# 2576.net
KiCad netlist of a schematic drawn in Altium Designer
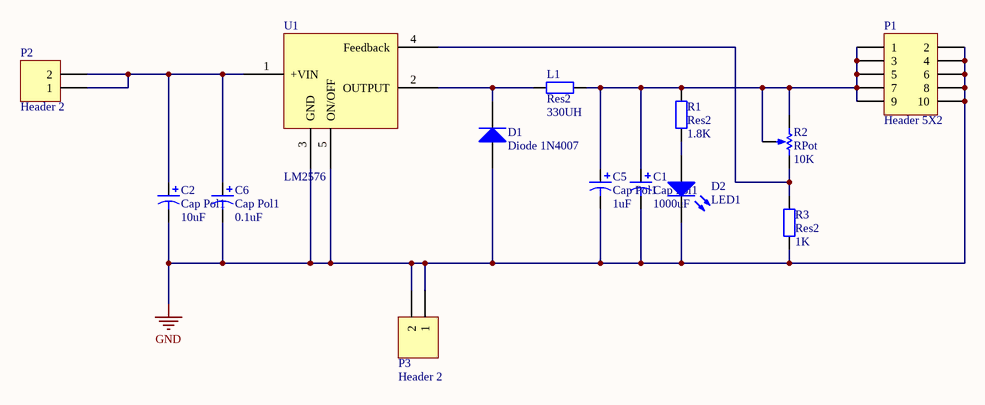
[diagram p0: 2576电压可调电路.SchDoc]

(export (version "E")
  (design (tool "Eeschema 10.0.6"))
  (components
    (comp (ref "C1")
      (value "Cap Pol1")
      (footprint "RAD-0.2")
      (description "Polarized Capacitor (Radial)")
      (fields (field (name "ALTIUM_VALUE") "1000uF") (field (name "PUBLISHER") "Altium Limited"))
      (libsource (lib "Miscellaneous Devices") (part "Cap Pol1"))
    )
    (comp (ref "C2")
      (value "Cap Pol1")
      (footprint "RAD-0.2")
      (description "Polarized Capacitor (Radial)")
      (fields (field (name "ALTIUM_VALUE") "10uF") (field (name "PUBLISHER") "Altium Limited"))
      (libsource (lib "Miscellaneous Devices") (part "Cap Pol1"))
    )
    (comp (ref "C5")
      (value "Cap Pol1")
      (footprint "RB7.6-15")
      (description "Polarized Capacitor (Radial)")
      (fields (field (name "ALTIUM_VALUE") "1uF") (field (name "PUBLISHER") "Altium Limited"))
      (libsource (lib "Miscellaneous Devices") (part "Cap Pol1"))
    )
    (comp (ref "C6")
      (value "Cap Pol1")
      (footprint "RB7.6-15")
      (description "Polarized Capacitor (Radial)")
      (fields (field (name "ALTIUM_VALUE") "0.1uF") (field (name "PUBLISHER") "Altium Limited"))
      (libsource (lib "Miscellaneous Devices") (part "Cap Pol1"))
    )
    (comp (ref "D1")
      (value "Diode 1N4007")
      (footprint "SMB")
      (description "1 Amp General Purpose Rectifier")
      (fields (field (name "PUBLISHER") "Altium Limited"))
      (libsource (lib "Miscellaneous Devices") (part "Diode 1N4007"))
    )
    (comp (ref "D2")
      (value "LED1")
      (footprint "LED-1")
      (description "Typical RED GaAs LED")
      (fields (field (name "PUBLISHER") "Altium Limited"))
      (libsource (lib "Miscellaneous Devices") (part "LED1"))
    )
    (comp (ref "L1")
      (value "Res2")
      (footprint "AXIAL-0.4")
      (description "Resistor")
      (fields (field (name "ALTIUM_VALUE") "330UH") (field (name "PUBLISHER") "Altium Limited"))
      (libsource (lib "Miscellaneous Devices") (part "Res2"))
    )
    (comp (ref "P1")
      (value "Header 5X2")
      (footprint "HDR2X5")
      (description "Header, 5-Pin, Dual row")
      (fields (field (name "PUBLISHER") "Altium Limited"))
      (libsource (lib "Miscellaneous Connectors") (part "Header 5X2"))
    )
    (comp (ref "P2")
      (value "Header 2")
      (footprint "HDR1X2")
      (description "Header, 2-Pin")
      (fields (field (name "PUBLISHER") "Altium Limited"))
      (libsource (lib "Miscellaneous Connectors") (part "Header 2"))
    )
    (comp (ref "P3")
      (value "Header 2")
      (footprint "HDR1X2")
      (description "Header, 2-Pin")
      (fields (field (name "PUBLISHER") "Altium Limited"))
      (libsource (lib "") (part "Header 2_1"))
    )
    (comp (ref "R1")
      (value "Res2")
      (footprint "AXIAL-0.4")
      (description "Resistor")
      (fields (field (name "ALTIUM_VALUE") "1.8K") (field (name "PUBLISHER") "Altium Limited"))
      (libsource (lib "") (part "Res2_1"))
    )
    (comp (ref "R2")
      (value "RPot")
      (footprint "VR5")
      (description "Potentiometer")
      (fields (field (name "ALTIUM_VALUE") "10K") (field (name "PUBLISHER") "Altium Limited"))
      (libsource (lib "Miscellaneous Devices") (part "RPot"))
    )
    (comp (ref "R3")
      (value "Res2")
      (footprint "AXIAL-0.4")
      (description "Resistor")
      (fields (field (name "ALTIUM_VALUE") "1K") (field (name "PUBLISHER") "Altium Limited"))
      (libsource (lib "") (part "Res2_1"))
    )
    (comp (ref "U1") (value "LM2576") (footprint "LM2576") (libsource (lib "LM2576") (part "LM2576")))
  )
  (nets
    (net (code "1") (name "GND") (class "Default")
      (node (ref "C1") (pin "2") (pinfunction "2_2") (pintype "passive"))
      (node (ref "C2") (pin "2") (pinfunction "2_2") (pintype "passive"))
      (node (ref "C5") (pin "2") (pinfunction "2_2") (pintype "passive"))
      (node (ref "C6") (pin "2") (pinfunction "2_2") (pintype "passive"))
      (node (ref "D1") (pin "1") (pinfunction "A_1") (pintype "passive"))
      (node (ref "D2") (pin "2") (pinfunction "K_2") (pintype "passive"))
      (node (ref "P1") (pin "10") (pinfunction "10_10") (pintype "passive"))
      (node (ref "P1") (pin "2") (pinfunction "2_2") (pintype "passive"))
      (node (ref "P1") (pin "4") (pinfunction "4_4") (pintype "passive"))
      (node (ref "P1") (pin "6") (pinfunction "6_6") (pintype "passive"))
      (node (ref "P1") (pin "8") (pinfunction "8_8") (pintype "passive"))
      (node (ref "P3") (pin "1") (pinfunction "1_1") (pintype "passive"))
      (node (ref "P3") (pin "2") (pinfunction "2_2") (pintype "passive"))
      (node (ref "R3") (pin "1") (pinfunction "1_1") (pintype "passive"))
      (node (ref "U1") (pin "3") (pinfunction "GND_3") (pintype "passive"))
      (node (ref "U1") (pin "5") (pinfunction "ON/OFF_5") (pintype "passive"))
    )
    (net (code "2") (name "Net-(D1-K)") (class "Default")
      (node (ref "D1") (pin "2") (pinfunction "K_2") (pintype "passive"))
      (node (ref "L1") (pin "1") (pinfunction "1_1") (pintype "passive"))
      (node (ref "U1") (pin "2") (pinfunction "OUTPUT_2") (pintype "passive"))
    )
    (net (code "3") (name "Net-(D2-A)") (class "Default")
      (node (ref "D2") (pin "1") (pinfunction "A_1") (pintype "passive"))
      (node (ref "R1") (pin "1") (pinfunction "1_1") (pintype "passive"))
    )
    (net (code "4") (name "Net-(R2-BOT)") (class "Default")
      (node (ref "R2") (pin "2") (pinfunction "BOT_2") (pintype "passive"))
      (node (ref "R3") (pin "2") (pinfunction "2_2") (pintype "passive"))
      (node (ref "U1") (pin "4") (pinfunction "Feedback_4") (pintype "passive"))
    )
    (net (code "5") (name "Net-(R2-TAP)") (class "Default")
      (node (ref "C1") (pin "1") (pinfunction "1_1") (pintype "passive"))
      (node (ref "C5") (pin "1") (pinfunction "1_1") (pintype "passive"))
      (node (ref "L1") (pin "2") (pinfunction "2_2") (pintype "passive"))
      (node (ref "P1") (pin "1") (pinfunction "1_1") (pintype "passive"))
      (node (ref "P1") (pin "3") (pinfunction "3_3") (pintype "passive"))
      (node (ref "P1") (pin "5") (pinfunction "5_5") (pintype "passive"))
      (node (ref "P1") (pin "7") (pinfunction "7_7") (pintype "passive"))
      (node (ref "P1") (pin "9") (pinfunction "9_9") (pintype "passive"))
      (node (ref "R1") (pin "2") (pinfunction "2_2") (pintype "passive"))
      (node (ref "R2") (pin "1") (pinfunction "TOP_1") (pintype "passive"))
      (node (ref "R2") (pin "3") (pinfunction "TAP_3") (pintype "passive"))
    )
    (net (code "6") (name "Net-(U1-+VIN)") (class "Default")
      (node (ref "C2") (pin "1") (pinfunction "1_1") (pintype "passive"))
      (node (ref "C6") (pin "1") (pinfunction "1_1") (pintype "passive"))
      (node (ref "P2") (pin "1") (pinfunction "1_1") (pintype "passive"))
      (node (ref "P2") (pin "2") (pinfunction "2_2") (pintype "passive"))
      (node (ref "U1") (pin "1") (pinfunction "+VIN_1") (pintype "passive"))
    )
  )
)
